# Power.net
KiCad netlist of a schematic drawn in Altium Designer
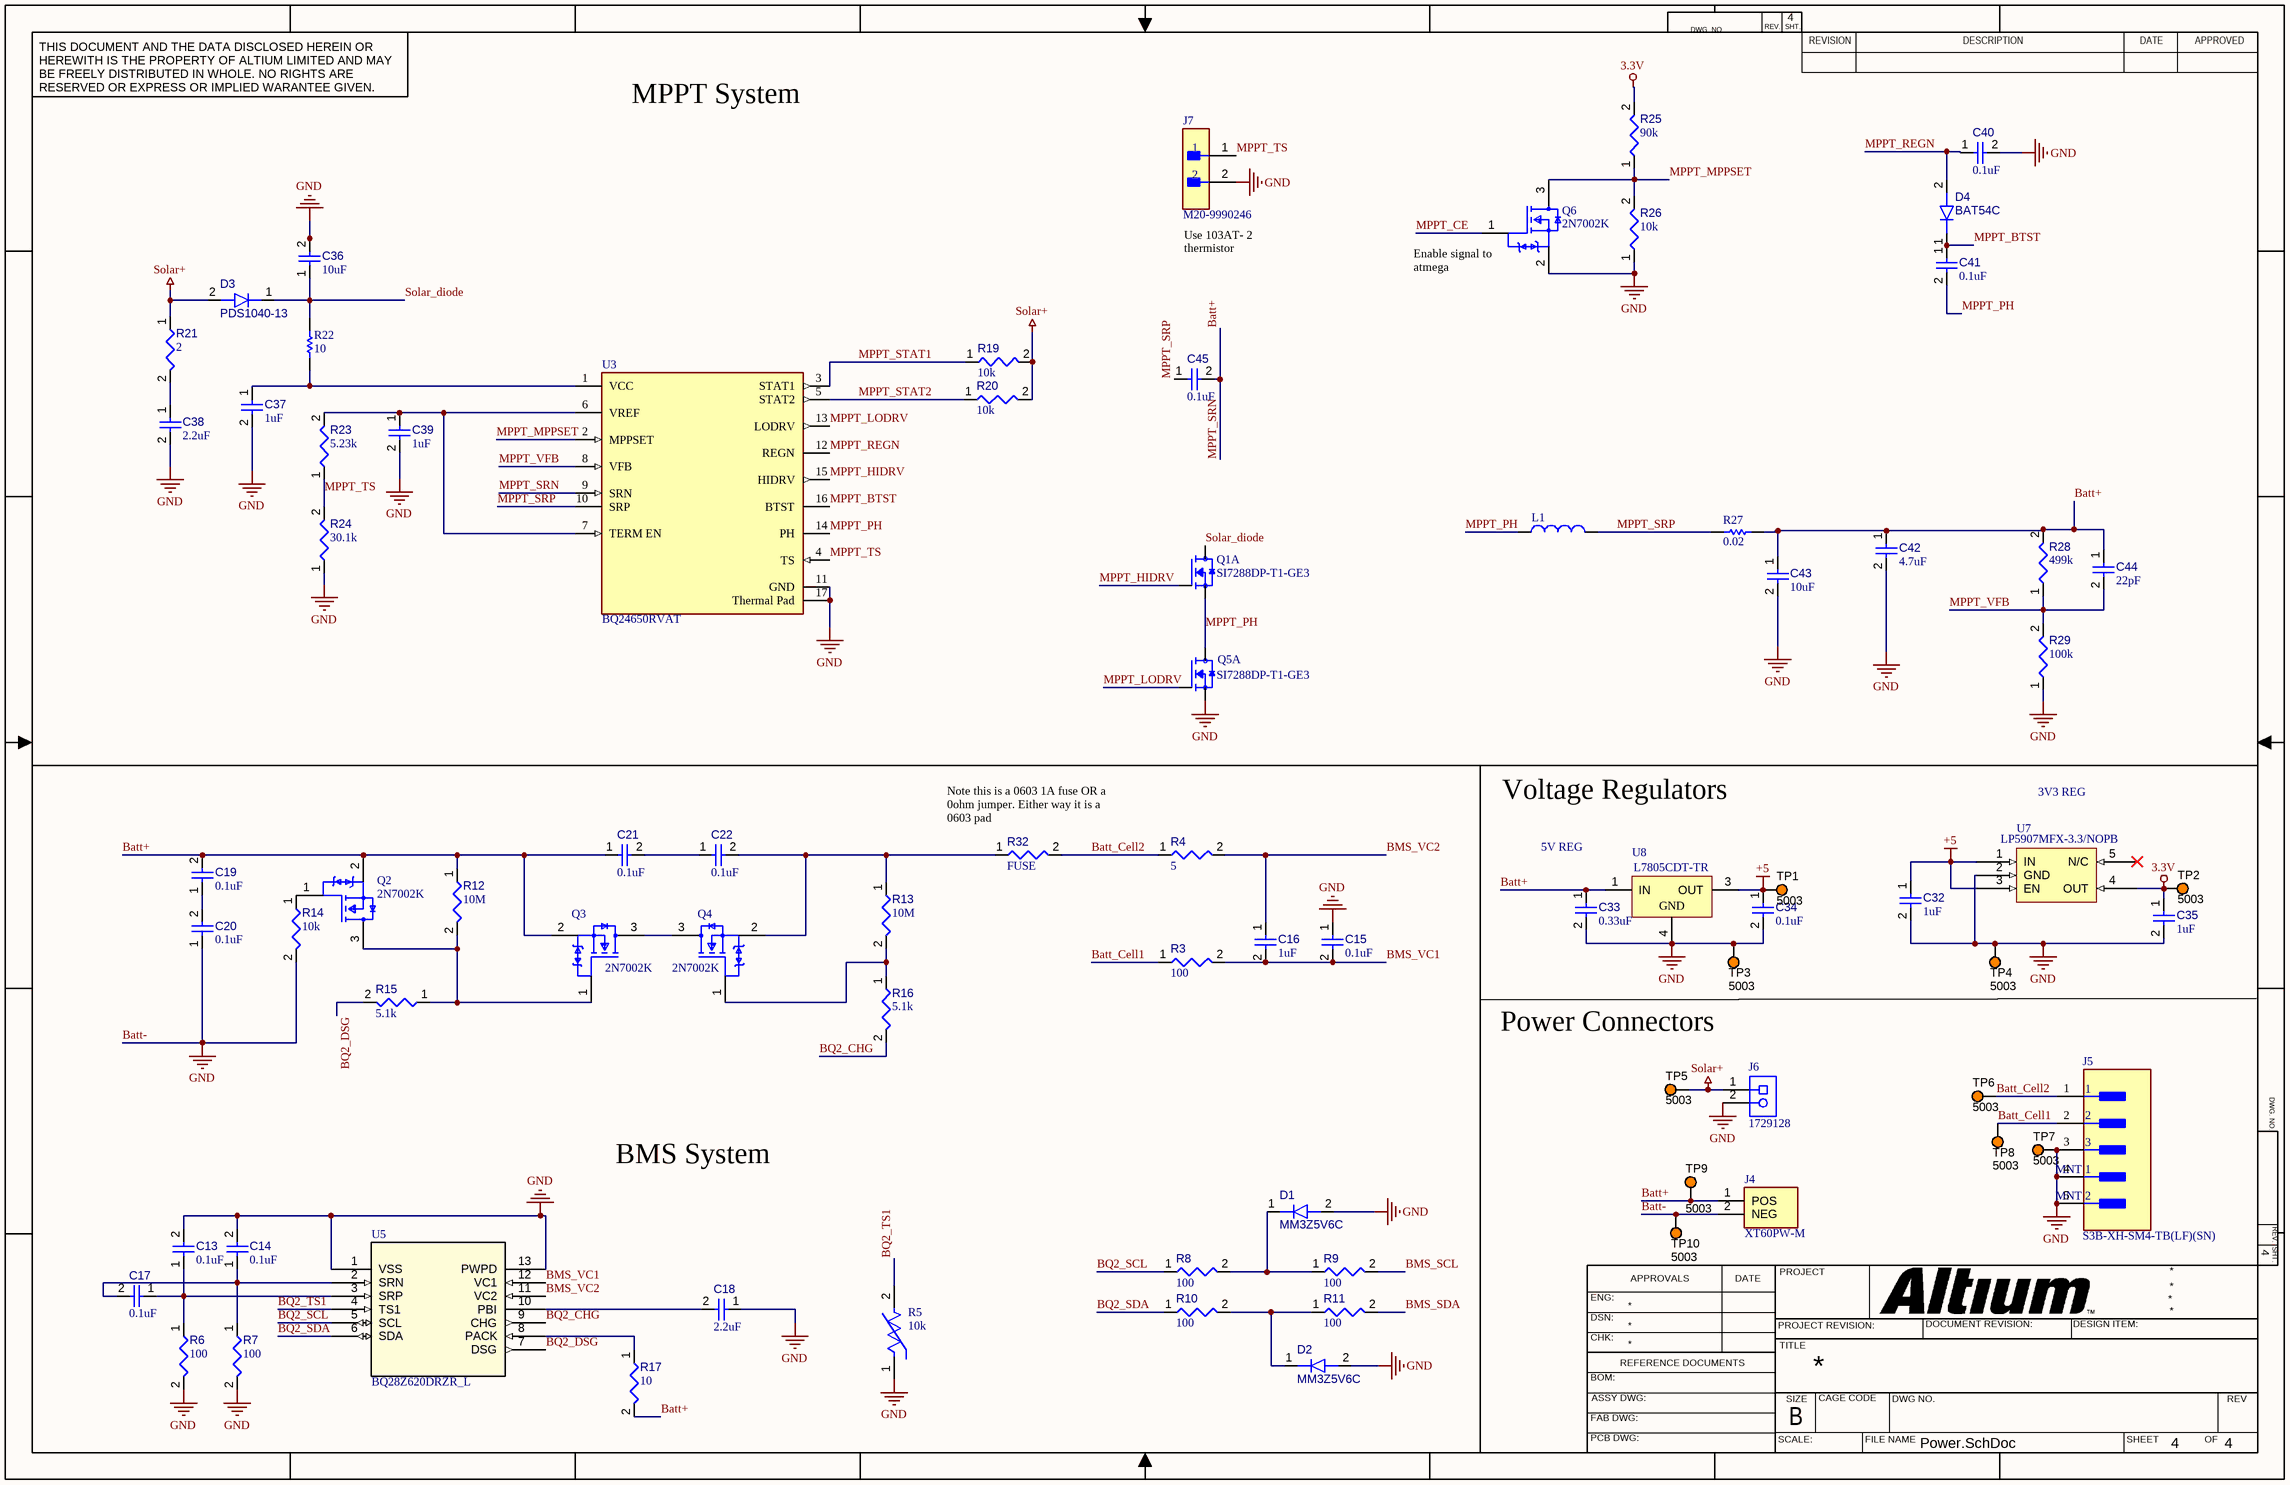
[diagram p0: Power.SchDoc]

(export (version "E")
  (design (tool "Eeschema 10.0.6"))
  (components
    (comp (ref "C13")
      (value "0.1uF")
      (footprint "CAPC1608X90X40NL10T20")
      (description "Chip Capacitor, 100 nF, +/- 10%, 50 V, 0603 (1608 Metric)")
      (fields (field (name "TOLERANCE") "10%") (field (name "Comment") "Capacitor 100 nF +/-10% 50 V 0603"))
      (libsource (lib "University of Michigan") (part "CAP-NP-2"))
    )
    (comp (ref "C14")
      (value "0.1uF")
      (footprint "CAPC1608X90X40NL10T20")
      (description "Chip Capacitor, 100 nF, +/- 10%, 50 V, 0603 (1608 Metric)")
      (fields (field (name "TOLERANCE") "10%") (field (name "Comment") "Capacitor 100 nF +/-10% 50 V 0603"))
      (libsource (lib "University of Michigan") (part "CAP-NP-2"))
    )
    (comp (ref "C15")
      (value "0.1uF")
      (footprint "CAPC1608X90X40NL10T20")
      (description "Chip Capacitor, 100 nF, +/- 10%, 50 V, 0603 (1608 Metric)")
      (fields (field (name "TOLERANCE") "10%") (field (name "Comment") "Capacitor 100 nF +/-10% 50 V 0603"))
      (libsource (lib "University of Michigan") (part "CAP-NP-2"))
    )
    (comp (ref "C16")
      (value "1uF")
      (footprint "CAPC1608X90X40NL10T20")
      (description "Chip Capacitor, 100 nF, +/- 10%, 50 V, 0603 (1608 Metric)")
      (fields (field (name "TOLERANCE") "10%") (field (name "Comment") "Capacitor 100 nF +/-10% 50 V 0603"))
      (libsource (lib "University of Michigan") (part "CAP-NP-2"))
    )
    (comp (ref "C17")
      (value "0.1uF")
      (footprint "CAPC1608X90X40NL10T20")
      (description "Chip Capacitor, 100 nF, +/- 10%, 50 V, 0603 (1608 Metric)")
      (fields (field (name "TOLERANCE") "10%") (field (name "Comment") "Capacitor 100 nF +/-10% 50 V 0603"))
      (libsource (lib "University of Michigan") (part "CAP-NP-2"))
    )
    (comp (ref "C18")
      (value "2.2uF")
      (footprint "CAPC1608X90X40NL10T20")
      (description "Chip Capacitor, 100 nF, +/- 10%, 50 V, 0603 (1608 Metric)")
      (fields (field (name "TOLERANCE") "10%") (field (name "Comment") "Capacitor 100 nF +/-10% 50 V 0603"))
      (libsource (lib "University of Michigan") (part "CAP-NP-2"))
    )
    (comp (ref "C19")
      (value "0.1uF")
      (footprint "CAPC1608X90X40NL10T20")
      (description "Chip Capacitor, 100 nF, +/- 10%, 50 V, 0603 (1608 Metric)")
      (fields (field (name "TOLERANCE") "10%") (field (name "Comment") "Capacitor 100 nF +/-10% 50 V 0603"))
      (libsource (lib "University of Michigan") (part "CAP-NP-2"))
    )
    (comp (ref "C20")
      (value "0.1uF")
      (footprint "CAPC1608X90X40NL10T20")
      (description "Chip Capacitor, 100 nF, +/- 10%, 50 V, 0603 (1608 Metric)")
      (fields (field (name "TOLERANCE") "10%") (field (name "Comment") "Capacitor 100 nF +/-10% 50 V 0603"))
      (libsource (lib "University of Michigan") (part "CAP-NP-2"))
    )
    (comp (ref "C21")
      (value "0.1uF")
      (footprint "CAPC1608X90X40NL10T20")
      (description "Chip Capacitor, 100 nF, +/- 10%, 50 V, 0603 (1608 Metric)")
      (fields (field (name "TOLERANCE") "10%") (field (name "Comment") "Capacitor 100 nF +/-10% 50 V 0603"))
      (libsource (lib "University of Michigan") (part "CAP-NP-2"))
    )
    (comp (ref "C22")
      (value "0.1uF")
      (footprint "CAPC1608X90X40NL10T20")
      (description "Chip Capacitor, 100 nF, +/- 10%, 50 V, 0603 (1608 Metric)")
      (fields (field (name "TOLERANCE") "10%") (field (name "Comment") "Capacitor 100 nF +/-10% 50 V 0603"))
      (libsource (lib "University of Michigan") (part "CAP-NP-2"))
    )
    (comp (ref "C32")
      (value "1uF")
      (footprint "CAPC1608X90X40NL10T20")
      (description "Chip Capacitor, 100 nF, +/- 10%, 50 V, 0603 (1608 Metric)")
      (fields (field (name "TOLERANCE") "10%") (field (name "Comment") "Capacitor 100 nF +/-10% 50 V 0603"))
      (libsource (lib "University of Michigan") (part "CAP-NP-2"))
    )
    (comp (ref "C33")
      (value "0.33uF")
      (footprint "CAPC1608X90X40NL10T20")
      (description "Chip Capacitor, 100 nF, +/- 10%, 50 V, 0603 (1608 Metric)")
      (fields (field (name "TOLERANCE") "10%") (field (name "Comment") "Capacitor 100 nF +/-10% 50 V 0603"))
      (libsource (lib "University of Michigan") (part "CAP-NP-2"))
    )
    (comp (ref "C34")
      (value "0.1uF")
      (footprint "CAPC1608X90X40NL10T20")
      (description "Chip Capacitor, 100 nF, +/- 10%, 50 V, 0603 (1608 Metric)")
      (fields (field (name "TOLERANCE") "10%") (field (name "Comment") "Capacitor 100 nF +/-10% 50 V 0603"))
      (libsource (lib "University of Michigan") (part "CAP-NP-2"))
    )
    (comp (ref "C35")
      (value "1uF")
      (footprint "CAPC1608X90X40NL10T20")
      (description "Chip Capacitor, 100 nF, +/- 10%, 50 V, 0603 (1608 Metric)")
      (fields (field (name "TOLERANCE") "10%") (field (name "Comment") "Capacitor 100 nF +/-10% 50 V 0603"))
      (libsource (lib "University of Michigan") (part "CAP-NP-2"))
    )
    (comp (ref "C36")
      (value "10uF")
      (footprint "FP-CGA6P-IPC_B")
      (fields (field (name "Comment") "CGA6M3X7R2E104K200AE"))
      (libsource (lib "University of Michigan") (part "CAP-NP-2"))
    )
    (comp (ref "C37")
      (value "1uF")
      (footprint "CAPC1608X90X40NL10T20")
      (description "Chip Capacitor, 100 nF, +/- 10%, 50 V, 0603 (1608 Metric)")
      (fields (field (name "TOLERANCE") "10%") (field (name "Comment") "Capacitor 100 nF +/-10% 50 V 0603"))
      (libsource (lib "University of Michigan") (part "CAP-NP-2"))
    )
    (comp (ref "C38")
      (value "2.2uF")
      (footprint "FP-CGA6P-IPC_B")
      (fields (field (name "Comment") "CGA6M3X7R2E104K200AE"))
      (libsource (lib "University of Michigan") (part "CAP-NP-2"))
    )
    (comp (ref "C39")
      (value "1uF")
      (footprint "CAPC1608X90X40NL10T20")
      (description "Chip Capacitor, 100 nF, +/- 10%, 50 V, 0603 (1608 Metric)")
      (fields (field (name "TOLERANCE") "10%") (field (name "Comment") "Capacitor 100 nF +/-10% 50 V 0603"))
      (libsource (lib "University of Michigan") (part "CAP-NP-2"))
    )
    (comp (ref "C40")
      (value "0.1uF")
      (footprint "CAPC1608X90X40NL10T20")
      (description "Chip Capacitor, 100 nF, +/- 10%, 50 V, 0603 (1608 Metric)")
      (fields (field (name "TOLERANCE") "10%") (field (name "Comment") "Capacitor 100 nF +/-10% 50 V 0603"))
      (libsource (lib "University of Michigan") (part "CAP-NP-2"))
    )
    (comp (ref "C41")
      (value "0.1uF")
      (footprint "CAPC1608X90X40NL10T20")
      (description "Chip Capacitor, 100 nF, +/- 10%, 50 V, 0603 (1608 Metric)")
      (fields (field (name "TOLERANCE") "10%") (field (name "Comment") "Capacitor 100 nF +/-10% 50 V 0603"))
      (libsource (lib "University of Michigan") (part "CAP-NP-2"))
    )
    (comp (ref "C42")
      (value "4.7uF")
      (footprint "FP-CGA6P-IPC_B")
      (fields (field (name "Comment") "CGA6M3X7R2E104K200AE"))
      (libsource (lib "University of Michigan") (part "CAP-NP-2"))
    )
    (comp (ref "C43")
      (value "10uF")
      (footprint "FP-CGA6P-IPC_B")
      (fields (field (name "Comment") "CGA6M3X7R2E104K200AE"))
      (libsource (lib "University of Michigan") (part "CAP-NP-2"))
    )
    (comp (ref "C44")
      (value "22pF")
      (footprint "CAPC1608X90X40NL10T20")
      (description "Chip Capacitor, 100 nF, +/- 10%, 50 V, 0603 (1608 Metric)")
      (fields (field (name "TOLERANCE") "10%") (field (name "Comment") "Capacitor 100 nF +/-10% 50 V 0603"))
      (libsource (lib "University of Michigan") (part "CAP-NP-2"))
    )
    (comp (ref "C45")
      (value "0.1uF")
      (footprint "CAPC1608X90X40NL10T20")
      (description "Chip Capacitor, 100 nF, +/- 10%, 50 V, 0603 (1608 Metric)")
      (fields (field (name "TOLERANCE") "10%") (field (name "Comment") "Capacitor 100 nF +/-10% 50 V 0603"))
      (libsource (lib "University of Michigan") (part "CAP-NP-2"))
    )
    (comp (ref "D1")
      (value "MM3Z5V6C")
      (footprint "FP-SOD-323F-MFG")
      (description "Zener Diode, 5.6V V(Z), 5%, 0.2W, Silicon, Unidirectional")
      (libsource (lib "University of Michigan") (part "DIODE-2"))
    )
    (comp (ref "D2")
      (value "MM3Z5V6C")
      (footprint "FP-SOD-323F-MFG")
      (description "Zener Diode, 5.6V V(Z), 5%, 0.2W, Silicon, Unidirectional")
      (libsource (lib "University of Michigan") (part "DIODE-2"))
    )
    (comp (ref "D3")
      (value "PDS1040-13")
      (footprint "FP-PowerDI5-MFG")
      (description "Rectifier Diode, Schottky, 1 Phase, 1 Element, 10A, 40V V(RRM), Silicon")
      (libsource (lib "University of Michigan") (part "DIODE-2"))
    )
    (comp (ref "D4")
      (value "BAT54C")
      (footprint "NXP-SOT23-3_V")
      (description "Rectifier Diode, Schottky, 2 Element, 0.2A, 30V V(RRM), Silicon, TO-236AB")
      (libsource (lib "University of Michigan") (part "DIODE-2"))
    )
    (comp (ref "J4")
      (value "XT60PW-M")
      (footprint "AMASS_XT60PW-M")
      (description "Socket, DC supply, male, PIN: 2")
      (fields (field (name "MF") "AMASS"))
      (libsource (lib "University of Michigan") (part "XT60PW-M"))
    )
    (comp (ref "J5")
      (value "S3B-XH-SM4-TB(LF)(SN)")
      (footprint "FP-S3B-XH-SM4-TB_LF_SN-MFG")
      (description "Conn Shrouded Header HDR 3 POS 2.5mm Solder RA Side Entry SMD T/R")
      (libsource (lib "University of Michigan") (part "49575d61908034f7a5505a4f8bf3aa4"))
    )
    (comp (ref "J6")
      (value "1729128")
      (footprint "PHOE-1729128-2_V")
      (description "Barrier Strip Terminal Block, 13.5A, 1.5mm2, 1 Row(s), 1 Deck(s)")
      (libsource (lib "University of Michigan") (part "CN-2P-F-R2"))
    )
    (comp (ref "J7")
      (value "M20-9990246")
      (footprint "FP-M20-9990246-MFG")
      (libsource (lib "University of Michigan") (part "3bc925449376181038e59eaffc5286c"))
    )
    (comp (ref "L1")
      (value "IHLP2525CZER100M01")
      (footprint "VISH-IHLP2525C-01_V")
      (description "General Purpose Inductor, 10uH, 20%, 1 Element, Composite-Core, SMD, 2525")
      (fields (field (name "TOLERANCE") "20%"))
      (libsource (lib "University of Michigan") (part "IND-2"))
    )
    (comp (ref "Q1")
      (value "SI7288DP-T1-GE3")
      (footprint "TRANS_SI7288DP-T1-GE3")
      (description "Mosfet Array 2 N-Channel (Dual) 40V 20A 15.6W Surface Mount PowerPAKÂ® SO-8 Dual")
      (fields (field (name "MF") "Vishay") (field (name "DIGI-KEY_PART_NUMBER") "SI7288DP-T1-GE3TR-ND"))
      (libsource (lib "University of Michigan") (part "SI7288DP-T1-GE3"))
    )
    (comp (ref "Q2")
      (value "2N7002K")
      (footprint "FP-318-08-IPC_C")
      (libsource (lib "University of Michigan") (part "40bafa8609a25cdbb0dab398ef4a0d9"))
    )
    (comp (ref "Q3")
      (value "2N7002K")
      (footprint "FP-318-08-IPC_C")
      (libsource (lib "University of Michigan") (part "40bafa8609a25cdbb0dab398ef4a0d9"))
    )
    (comp (ref "Q4")
      (value "2N7002K")
      (footprint "FP-318-08-IPC_C")
      (libsource (lib "University of Michigan") (part "40bafa8609a25cdbb0dab398ef4a0d9"))
    )
    (comp (ref "Q5")
      (value "SI7288DP-T1-GE3")
      (footprint "TRANS_SI7288DP-T1-GE3")
      (description "Mosfet Array 2 N-Channel (Dual) 40V 20A 15.6W Surface Mount PowerPAKÂ® SO-8 Dual")
      (fields (field (name "MF") "Vishay") (field (name "DIGI-KEY_PART_NUMBER") "SI7288DP-T1-GE3TR-ND"))
      (libsource (lib "University of Michigan") (part "SI7288DP-T1-GE3"))
    )
    (comp (ref "Q6")
      (value "2N7002K")
      (footprint "FP-318-08-IPC_C")
      (libsource (lib "University of Michigan") (part "40bafa8609a25cdbb0dab398ef4a0d9"))
    )
    (comp (ref "R3")
      (value "100")
      (footprint "RESC0603(1608)_L")
      (description "Chip Resistor, 120 Ohms, +/-5 %, 0.1 W, -55 to 155 degC, 0603")
      (fields (field (name "POWER") "100mW") (field (name "TOLERANCE") "5%"))
      (libsource (lib "University of Michigan") (part "RES-2"))
    )
    (comp (ref "R4")
      (value "5")
      (footprint "RESC0603(1608)_L")
      (description "Chip Resistor, 120 Ohms, +/-5 %, 0.1 W, -55 to 155 degC, 0603")
      (fields (field (name "POWER") "100mW") (field (name "TOLERANCE") "5%"))
      (libsource (lib "University of Michigan") (part "RES-2"))
    )
    (comp (ref "R5")
      (value "10k")
      (footprint "FP-103AT-2-MFG")
      (description "NTC Thermistor, 10000ohm, Through Hole Mount")
      (fields (field (name "POWER") "10mW") (field (name "TOLERANCE") "1%"))
      (libsource (lib "University of Michigan") (part "3b148a6ebabc5fb4d708a66c052d352"))
    )
    (comp (ref "R6")
      (value "100")
      (footprint "RESC0603(1608)_L")
      (description "Chip Resistor, 120 Ohms, +/-5 %, 0.1 W, -55 to 155 degC, 0603")
      (fields (field (name "POWER") "100mW") (field (name "TOLERANCE") "5%"))
      (libsource (lib "University of Michigan") (part "RES-2"))
    )
    (comp (ref "R7")
      (value "100")
      (footprint "RESC0603(1608)_L")
      (description "Chip Resistor, 120 Ohms, +/-5 %, 0.1 W, -55 to 155 degC, 0603")
      (fields (field (name "POWER") "100mW") (field (name "TOLERANCE") "5%"))
      (libsource (lib "University of Michigan") (part "RES-2"))
    )
    (comp (ref "R8")
      (value "100")
      (footprint "RESC0603(1608)_L")
      (description "Chip Resistor, 120 Ohms, +/-5 %, 0.1 W, -55 to 155 degC, 0603")
      (fields (field (name "POWER") "100mW") (field (name "TOLERANCE") "5%"))
      (libsource (lib "University of Michigan") (part "RES-2"))
    )
    (comp (ref "R9")
      (value "100")
      (footprint "RESC0603(1608)_L")
      (description "Chip Resistor, 120 Ohms, +/-5 %, 0.1 W, -55 to 155 degC, 0603")
      (fields (field (name "POWER") "100mW") (field (name "TOLERANCE") "5%"))
      (libsource (lib "University of Michigan") (part "RES-2"))
    )
    (comp (ref "R10")
      (value "100")
      (footprint "RESC0603(1608)_L")
      (description "Chip Resistor, 120 Ohms, +/-5 %, 0.1 W, -55 to 155 degC, 0603")
      (fields (field (name "POWER") "100mW") (field (name "TOLERANCE") "5%"))
      (libsource (lib "University of Michigan") (part "RES-2"))
    )
    (comp (ref "R11")
      (value "100")
      (footprint "RESC0603(1608)_L")
      (description "Chip Resistor, 120 Ohms, +/-5 %, 0.1 W, -55 to 155 degC, 0603")
      (fields (field (name "POWER") "100mW") (field (name "TOLERANCE") "5%"))
      (libsource (lib "University of Michigan") (part "RES-2"))
    )
    (comp (ref "R12")
      (value "10M")
      (footprint "RESC0603(1608)_L")
      (description "Chip Resistor, 120 Ohms, +/-5 %, 0.1 W, -55 to 155 degC, 0603")
      (fields (field (name "POWER") "100mW") (field (name "TOLERANCE") "5%"))
      (libsource (lib "University of Michigan") (part "RES-2"))
    )
    (comp (ref "R13")
      (value "10M")
      (footprint "RESC0603(1608)_L")
      (description "Chip Resistor, 120 Ohms, +/-5 %, 0.1 W, -55 to 155 degC, 0603")
      (fields (field (name "POWER") "100mW") (field (name "TOLERANCE") "5%"))
      (libsource (lib "University of Michigan") (part "RES-2"))
    )
    (comp (ref "R14")
      (value "10k")
      (footprint "RESC0603(1608)_L")
      (description "Chip Resistor, 120 Ohms, +/-5 %, 0.1 W, -55 to 155 degC, 0603")
      (fields (field (name "POWER") "100mW") (field (name "TOLERANCE") "5%"))
      (libsource (lib "University of Michigan") (part "RES-2"))
    )
    (comp (ref "R15")
      (value "5.1k")
      (footprint "RESC0603(1608)_L")
      (description "Chip Resistor, 120 Ohms, +/-5 %, 0.1 W, -55 to 155 degC, 0603")
      (fields (field (name "POWER") "100mW") (field (name "TOLERANCE") "5%"))
      (libsource (lib "University of Michigan") (part "RES-2"))
    )
    (comp (ref "R16")
      (value "5.1k")
      (footprint "RESC0603(1608)_L")
      (description "Chip Resistor, 120 Ohms, +/-5 %, 0.1 W, -55 to 155 degC, 0603")
      (fields (field (name "POWER") "100mW") (field (name "TOLERANCE") "5%"))
      (libsource (lib "University of Michigan") (part "RES-2"))
    )
    (comp (ref "R17")
      (value "10")
      (footprint "RESC0603(1608)_L")
      (description "Chip Resistor, 120 Ohms, +/-5 %, 0.1 W, -55 to 155 degC, 0603")
      (fields (field (name "POWER") "100mW") (field (name "TOLERANCE") "5%"))
      (libsource (lib "University of Michigan") (part "RES-2"))
    )
    (comp (ref "R19")
      (value "10k")
      (footprint "RESC0603(1608)_L")
      (description "Chip Resistor, 120 Ohms, +/-5 %, 0.1 W, -55 to 155 degC, 0603")
      (fields (field (name "POWER") "100mW") (field (name "TOLERANCE") "5%"))
      (libsource (lib "University of Michigan") (part "RES-2"))
    )
    (comp (ref "R20")
      (value "10k")
      (footprint "RESC0603(1608)_L")
      (description "Chip Resistor, 120 Ohms, +/-5 %, 0.1 W, -55 to 155 degC, 0603")
      (fields (field (name "POWER") "100mW") (field (name "TOLERANCE") "5%"))
      (libsource (lib "University of Michigan") (part "RES-2"))
    )
    (comp (ref "R21")
      (value "2")
      (footprint "FP-CRCW2512-e3-MFG")
      (fields
        (field (name "TOLERANCE") "5%")
        (field (name "POWER") "1W")
        (field (name "Comment") "CRCW251291R0JNEG")
      )
      (libsource (lib "University of Michigan") (part "RES-2"))
    )
    (comp (ref "R22")
      (value "10")
      (footprint "RESC3116X70X50ML13T20")
      (description "Chip Resistor, 0 Ohm, 0.25 W, -55 to 155 degC, 1206 (3216 Metric)")
      (fields (field (name "TOLERANCE") "0.05%") (field (name "POWER") "250mW"))
      (libsource (lib "") (part "RES-2_1"))
    )
    (comp (ref "R23")
      (value "5.23k")
      (footprint "RESC0603(1608)_L")
      (description "Chip Resistor, 120 Ohms, +/-5 %, 0.1 W, -55 to 155 degC, 0603")
      (fields (field (name "POWER") "100mW") (field (name "TOLERANCE") "5%"))
      (libsource (lib "University of Michigan") (part "RES-2"))
    )
    (comp (ref "R24")
      (value "30.1k")
      (footprint "RESC0603(1608)_L")
      (description "Chip Resistor, 120 Ohms, +/-5 %, 0.1 W, -55 to 155 degC, 0603")
      (fields (field (name "POWER") "100mW") (field (name "TOLERANCE") "5%"))
      (libsource (lib "University of Michigan") (part "RES-2"))
    )
    (comp (ref "R25")
      (value "90k")
      (footprint "RESC0603(1608)_L")
      (description "Chip Resistor, 120 Ohms, +/-5 %, 0.1 W, -55 to 155 degC, 0603")
      (fields (field (name "POWER") "100mW") (field (name "TOLERANCE") "5%"))
      (libsource (lib "University of Michigan") (part "RES-2"))
    )
    (comp (ref "R26")
      (value "10k")
      (footprint "RESC0603(1608)_L")
      (description "Chip Resistor, 120 Ohms, +/-5 %, 0.1 W, -55 to 155 degC, 0603")
      (fields (field (name "POWER") "100mW") (field (name "TOLERANCE") "5%"))
      (libsource (lib "University of Michigan") (part "RES-2"))
    )
    (comp (ref "R27")
      (value "0.02")
      (footprint "RESC3116X70X50ML13T20")
      (description "Chip Resistor, 1 KOhm, +/- 1%, 0.25 W, -55 to 155 degC, 1206 (3216 Metric)")
      (fields (field (name "TOLERANCE") "1%") (field (name "POWER") "250mW"))
      (libsource (lib "") (part "RES-2_1"))
    )
    (comp (ref "R28")
      (value "499k")
      (footprint "RESC0603(1608)_L")
      (description "Chip Resistor, 120 Ohms, +/-5 %, 0.1 W, -55 to 155 degC, 0603")
      (fields (field (name "POWER") "100mW") (field (name "TOLERANCE") "5%"))
      (libsource (lib "University of Michigan") (part "RES-2"))
    )
    (comp (ref "R29")
      (value "100k")
      (footprint "RESC0603(1608)_L")
      (description "Chip Resistor, 120 Ohms, +/-5 %, 0.1 W, -55 to 155 degC, 0603")
      (fields (field (name "POWER") "100mW") (field (name "TOLERANCE") "5%"))
      (libsource (lib "University of Michigan") (part "RES-2"))
    )
    (comp (ref "R32")
      (value "FUSE")
      (footprint "RESC0603(1608)_L")
      (description "Chip Resistor, 120 Ohms, +/-5 %, 0.1 W, -55 to 155 degC, 0603")
      (fields (field (name "POWER") "100mW") (field (name "TOLERANCE") "5%"))
      (libsource (lib "University of Michigan") (part "RES-2"))
    )
    (comp (ref "TP1")
      (value "5003")
      (footprint "KSTN-5003")
      (description "Test Point, Orange, Height 4.6 mm, Tail Length 3 mm, 1-Pin THD, RoHS")
      (fields (field (name "MANUFACTURER") "Keystone"))
      (libsource (lib "University of Michigan") (part "TESTPOINT_ORANGE"))
    )
    (comp (ref "TP2")
      (value "5003")
      (footprint "KSTN-5003")
      (description "Test Point, Orange, Height 4.6 mm, Tail Length 3 mm, 1-Pin THD, RoHS")
      (fields (field (name "MANUFACTURER") "Keystone"))
      (libsource (lib "University of Michigan") (part "TESTPOINT_ORANGE"))
    )
    (comp (ref "TP3")
      (value "5003")
      (footprint "KSTN-5003")
      (description "Test Point, Orange, Height 4.6 mm, Tail Length 3 mm, 1-Pin THD, RoHS")
      (fields (field (name "MANUFACTURER") "Keystone"))
      (libsource (lib "University of Michigan") (part "TESTPOINT_ORANGE"))
    )
    (comp (ref "TP4")
      (value "5003")
      (footprint "KSTN-5003")
      (description "Test Point, Orange, Height 4.6 mm, Tail Length 3 mm, 1-Pin THD, RoHS")
      (fields (field (name "MANUFACTURER") "Keystone"))
      (libsource (lib "University of Michigan") (part "TESTPOINT_ORANGE"))
    )
    (comp (ref "TP5")
      (value "5003")
      (footprint "KSTN-5003")
      (description "Test Point, Orange, Height 4.6 mm, Tail Length 3 mm, 1-Pin THD, RoHS")
      (fields (field (name "MANUFACTURER") "Keystone"))
      (libsource (lib "University of Michigan") (part "TESTPOINT_ORANGE"))
    )
    (comp (ref "TP6")
      (value "5003")
      (footprint "KSTN-5003")
      (description "Test Point, Orange, Height 4.6 mm, Tail Length 3 mm, 1-Pin THD, RoHS")
      (fields (field (name "MANUFACTURER") "Keystone"))
      (libsource (lib "University of Michigan") (part "TESTPOINT_ORANGE"))
    )
    (comp (ref "TP7")
      (value "5003")
      (footprint "KSTN-5003")
      (description "Test Point, Orange, Height 4.6 mm, Tail Length 3 mm, 1-Pin THD, RoHS")
      (fields (field (name "MANUFACTURER") "Keystone"))
      (libsource (lib "University of Michigan") (part "TESTPOINT_ORANGE"))
    )
    (comp (ref "TP8")
      (value "5003")
      (footprint "KSTN-5003")
      (description "Test Point, Orange, Height 4.6 mm, Tail Length 3 mm, 1-Pin THD, RoHS")
      (fields (field (name "MANUFACTURER") "Keystone"))
      (libsource (lib "University of Michigan") (part "TESTPOINT_ORANGE"))
    )
    (comp (ref "TP9")
      (value "5003")
      (footprint "KSTN-5003")
      (description "Test Point, Orange, Height 4.6 mm, Tail Length 3 mm, 1-Pin THD, RoHS")
      (fields (field (name "MANUFACTURER") "Keystone"))
      (libsource (lib "University of Michigan") (part "TESTPOINT_ORANGE"))
    )
    (comp (ref "TP10")
      (value "5003")
      (footprint "KSTN-5003")
      (description "Test Point, Orange, Height 4.6 mm, Tail Length 3 mm, 1-Pin THD, RoHS")
      (fields (field (name "MANUFACTURER") "Keystone"))
      (libsource (lib "University of Michigan") (part "TESTPOINT_ORANGE"))
    )
    (comp (ref "U3")
      (value "BQ24650RVAT")
      (footprint "FP-RVA0016A-IPC_B")
      (description "Power Supply Support Circuit, Adjustable, 1 Channel, +3.85V, PQCC16")
      (libsource (lib "University of Michigan") (part "cf19bb46e92d87c2bf2948a47118a18"))
    )
    (comp (ref "U5")
      (value "BQ28Z620DRZR_L")
      (footprint "VSON12_DRZ_TEX_L")
      (description "No Description Available")
      (fields
        (field (name "MANUFACTURER_PART_NUMBER") "BQ28Z620DRZR")
        (field (name "COPYRIGHT") "Copyright (C) 2023 Ultra Librarian. All rights reserved.")
      )
      (libsource (lib "University of Michigan") (part "BQ28Z620DRZR_L"))
    )
    (comp (ref "U7")
      (value "LP5907MFX-3.3/NOPB")
      (footprint "FP-DBV0005A-IPC_B")
      (description "Fixed Positive LDO Regulator, 3.3V, 0.25V Dropout, PDSO5")
      (libsource (lib "University of Michigan") (part "LP5907MFX-3.3_NOPB-Symbol-1"))
    )
    (comp (ref "U8")
      (value "L7805CDT-TR")
      (footprint "TO-252_L")
      (description "Fixed Positive Standard Regulator, 5VBIPolar, PSSO2")
      (libsource (lib "University of Michigan") (part "PM-REG-L4940-SOT3"))
    )
  )
  (nets
    (net (code "1") (name "+5") (class "Default")
      (node (ref "C32") (pin "1") (pinfunction "1_1") (pintype "passive"))
      (node (ref "C34") (pin "1") (pinfunction "1_1") (pintype "passive"))
      (node (ref "TP1") (pin "1") (pinfunction "1_1") (pintype "passive"))
      (node (ref "U7") (pin "1") (pinfunction "IN_1") (pintype "input"))
      (node (ref "U7") (pin "3") (pinfunction "EN_3") (pintype "input"))
      (node (ref "U8") (pin "3") (pinfunction "OUT_3") (pintype "power_in"))
    )
    (net (code "2") (name "/BMS_SCL") (class "Default")
      (node (ref "R9") (pin "2") (pinfunction "2_2") (pintype "passive"))
    )
    (net (code "3") (name "/BMS_SDA") (class "Default")
      (node (ref "R11") (pin "2") (pinfunction "2_2") (pintype "passive"))
    )
    (net (code "4") (name "/BMS_VC1") (class "Default")
      (node (ref "C15") (pin "2") (pinfunction "2_2") (pintype "passive"))
      (node (ref "C16") (pin "2") (pinfunction "2_2") (pintype "passive"))
      (node (ref "R3") (pin "2") (pinfunction "2_2") (pintype "passive"))
      (node (ref "U5") (pin "12") (pinfunction "VC1_12") (pintype "input"))
    )
    (net (code "5") (name "/BMS_VC2") (class "Default")
      (node (ref "C16") (pin "1") (pinfunction "1_1") (pintype "passive"))
      (node (ref "R4") (pin "2") (pinfunction "2_2") (pintype "passive"))
      (node (ref "U5") (pin "11") (pinfunction "VC2_11") (pintype "input"))
    )
    (net (code "6") (name "/BQ2_CHG") (class "Default")
      (node (ref "R16") (pin "2") (pinfunction "2_2") (pintype "passive"))
      (node (ref "U5") (pin "9") (pinfunction "CHG_9") (pintype "output"))
    )
    (net (code "7") (name "/BQ2_DSG") (class "Default")
      (node (ref "R15") (pin "2") (pinfunction "2_2") (pintype "passive"))
      (node (ref "U5") (pin "7") (pinfunction "DSG_7") (pintype "output"))
    )
    (net (code "8") (name "/BQ2_SCL") (class "Default")
      (node (ref "R8") (pin "1") (pinfunction "1_1") (pintype "passive"))
      (node (ref "U5") (pin "5") (pinfunction "SCL_5") (pintype "bidirectional"))
    )
    (net (code "9") (name "/BQ2_SDA") (class "Default")
      (node (ref "R10") (pin "1") (pinfunction "1_1") (pintype "passive"))
      (node (ref "U5") (pin "6") (pinfunction "SDA_6") (pintype "bidirectional"))
    )
    (net (code "10") (name "/BQ2_TS1") (class "Default")
      (node (ref "R5") (pin "2") (pinfunction "2_2") (pintype "passive"))
      (node (ref "U5") (pin "4") (pinfunction "TS1_4") (pintype "input"))
    )
    (net (code "11") (name "/Batt+") (class "Default")
      (node (ref "C19") (pin "2") (pinfunction "2_2") (pintype "passive"))
      (node (ref "C21") (pin "1") (pinfunction "1_1") (pintype "passive"))
      (node (ref "C33") (pin "1") (pinfunction "1_1") (pintype "passive"))
      (node (ref "C42") (pin "1") (pinfunction "1_1") (pintype "passive"))
      (node (ref "C43") (pin "1") (pinfunction "1_1") (pintype "passive"))
      (node (ref "C44") (pin "1") (pinfunction "1_1") (pintype "passive"))
      (node (ref "C45") (pin "2") (pinfunction "2_2") (pintype "passive"))
      (node (ref "J4") (pin "1") (pinfunction "POS_1") (pintype "passive"))
      (node (ref "Q2") (pin "2") (pinfunction "Source_2") (pintype "passive"))
      (node (ref "Q3") (pin "2") (pinfunction "Source_2") (pintype "passive"))
      (node (ref "R12") (pin "1") (pinfunction "1_1") (pintype "passive"))
      (node (ref "R17") (pin "2") (pinfunction "2_2") (pintype "passive"))
      (node (ref "R27") (pin "2") (pinfunction "2_2") (pintype "passive"))
      (node (ref "R28") (pin "2") (pinfunction "2_2") (pintype "passive"))
      (node (ref "TP9") (pin "1") (pinfunction "1_1") (pintype "passive"))
      (node (ref "U3") (pin "9") (pinfunction "SRN_9") (pintype "input"))
      (node (ref "U8") (pin "1") (pinfunction "IN_1") (pintype "power_in"))
    )
    (net (code "12") (name "/Batt_Cell1") (class "Default")
      (node (ref "J5") (pin "2") (pinfunction "2_2") (pintype "passive"))
      (node (ref "R3") (pin "1") (pinfunction "1_1") (pintype "passive"))
      (node (ref "TP8") (pin "1") (pinfunction "1_1") (pintype "passive"))
    )
    (net (code "13") (name "/Batt_Cell2") (class "Default")
      (node (ref "J5") (pin "1") (pinfunction "1_1") (pintype "passive"))
      (node (ref "R32") (pin "2") (pinfunction "2_2") (pintype "passive"))
      (node (ref "R4") (pin "1") (pinfunction "1_1") (pintype "passive"))
      (node (ref "TP6") (pin "1") (pinfunction "1_1") (pintype "passive"))
    )
    (net (code "14") (name "/MPPT_BTST") (class "Default")
      (node (ref "C41") (pin "1") (pinfunction "1_1") (pintype "passive"))
      (node (ref "D4") (pin "1") (pinfunction "K_1") (pintype "passive"))
      (node (ref "U3") (pin "16") (pinfunction "BTST_16") (pintype "power_in"))
    )
    (net (code "15") (name "/MPPT_CE") (class "Default")
      (node (ref "Q6") (pin "1") (pinfunction "Gate_1") (pintype "passive"))
    )
    (net (code "16") (name "/MPPT_HIDRV") (class "Default")
      (node (ref "Q1") (pin "2") (pinfunction "G1_2") (pintype "passive"))
      (node (ref "U3") (pin "15") (pinfunction "HIDRV_15") (pintype "output"))
    )
    (net (code "17") (name "/MPPT_LODRV") (class "Default")
      (node (ref "Q5") (pin "2") (pinfunction "G1_2") (pintype "passive"))
      (node (ref "U3") (pin "13") (pinfunction "LODRV_13") (pintype "output"))
    )
    (net (code "18") (name "/MPPT_MPPSET") (class "Default")
      (node (ref "Q6") (pin "3") (pinfunction "Drain_3") (pintype "passive"))
      (node (ref "R25") (pin "1") (pinfunction "1_1") (pintype "passive"))
      (node (ref "R26") (pin "2") (pinfunction "2_2") (pintype "passive"))
      (node (ref "U3") (pin "2") (pinfunction "MPPSET_2") (pintype "input"))
    )
    (net (code "19") (name "/MPPT_PH") (class "Default")
      (node (ref "C41") (pin "2") (pinfunction "2_2") (pintype "passive"))
      (node (ref "L1") (pin "1") (pinfunction "1_1") (pintype "passive"))
      (node (ref "Q1") (pin "1") (pinfunction "S1_1") (pintype "passive"))
      (node (ref "Q5") (pin "7_8_9") (pinfunction "D1_7_8_9") (pintype "passive"))
      (node (ref "U3") (pin "14") (pinfunction "PH_14") (pintype "power_in"))
    )
    (net (code "20") (name "/MPPT_REGN") (class "Default")
      (node (ref "C40") (pin "1") (pinfunction "1_1") (pintype "passive"))
      (node (ref "D4") (pin "2") (pinfunction "A_2") (pintype "passive"))
      (node (ref "U3") (pin "12") (pinfunction "REGN_12") (pintype "power_in"))
    )
    (net (code "21") (name "/MPPT_SRP") (class "Default")
      (node (ref "C45") (pin "1") (pinfunction "1_1") (pintype "passive"))
      (node (ref "L1") (pin "2") (pinfunction "2_2") (pintype "passive"))
      (node (ref "R27") (pin "1") (pinfunction "1_1") (pintype "passive"))
      (node (ref "U3") (pin "10") (pinfunction "SRP_10") (pintype "passive"))
    )
    (net (code "22") (name "/MPPT_STAT1") (class "Default")
      (node (ref "R19") (pin "1") (pinfunction "1_1") (pintype "passive"))
      (node (ref "U3") (pin "3") (pinfunction "STAT1_3") (pintype "output"))
    )
    (net (code "23") (name "/MPPT_STAT2") (class "Default")
      (node (ref "R20") (pin "1") (pinfunction "1_1") (pintype "passive"))
      (node (ref "U3") (pin "5") (pinfunction "STAT2_5") (pintype "output"))
    )
    (net (code "24") (name "/MPPT_TS") (class "Default")
      (node (ref "J7") (pin "1") (pinfunction "1_1") (pintype "passive"))
      (node (ref "R23") (pin "1") (pinfunction "1_1") (pintype "passive"))
      (node (ref "R24") (pin "2") (pinfunction "2_2") (pintype "passive"))
      (node (ref "U3") (pin "4") (pinfunction "TS_4") (pintype "input"))
    )
    (net (code "25") (name "/MPPT_VFB") (class "Default")
      (node (ref "C44") (pin "2") (pinfunction "2_2") (pintype "passive"))
      (node (ref "R28") (pin "1") (pinfunction "1_1") (pintype "passive"))
      (node (ref "R29") (pin "2") (pinfunction "2_2") (pintype "passive"))
      (node (ref "U3") (pin "8") (pinfunction "VFB_8") (pintype "input"))
    )
    (net (code "26") (name "/Solar_diode") (class "Default")
      (node (ref "C36") (pin "1") (pinfunction "1_1") (pintype "passive"))
      (node (ref "D3") (pin "1") (pinfunction "K_1") (pintype "passive"))
      (node (ref "Q1") (pin "7_8_9") (pinfunction "D1_7_8_9") (pintype "passive"))
      (node (ref "R22") (pin "1") (pinfunction "1_1") (pintype "passive"))
    )
    (net (code "27") (name "3.3V") (class "Default")
      (node (ref "C35") (pin "1") (pinfunction "1_1") (pintype "passive"))
      (node (ref "R25") (pin "2") (pinfunction "2_2") (pintype "passive"))
      (node (ref "TP2") (pin "1") (pinfunction "1_1") (pintype "passive"))
      (node (ref "U7") (pin "4") (pinfunction "OUT_4") (pintype "input"))
    )
    (net (code "28") (name "GND") (class "Default")
      (node (ref "C13") (pin "2") (pinfunction "2_2") (pintype "passive"))
      (node (ref "C14") (pin "2") (pinfunction "2_2") (pintype "passive"))
      (node (ref "C15") (pin "1") (pinfunction "1_1") (pintype "passive"))
      (node (ref "C18") (pin "1") (pinfunction "1_1") (pintype "passive"))
      (node (ref "C20") (pin "1") (pinfunction "1_1") (pintype "passive"))
      (node (ref "C32") (pin "2") (pinfunction "2_2") (pintype "passive"))
      (node (ref "C33") (pin "2") (pinfunction "2_2") (pintype "passive"))
      (node (ref "C34") (pin "2") (pinfunction "2_2") (pintype "passive"))
      (node (ref "C35") (pin "2") (pinfunction "2_2") (pintype "passive"))
      (node (ref "C36") (pin "2") (pinfunction "2_2") (pintype "passive"))
      (node (ref "C37") (pin "2") (pinfunction "2_2") (pintype "passive"))
      (node (ref "C38") (pin "2") (pinfunction "2_2") (pintype "passive"))
      (node (ref "C39") (pin "2") (pinfunction "2_2") (pintype "passive"))
      (node (ref "C40") (pin "2") (pinfunction "2_2") (pintype "passive"))
      (node (ref "C42") (pin "2") (pinfunction "2_2") (pintype "passive"))
      (node (ref "C43") (pin "2") (pinfunction "2_2") (pintype "passive"))
      (node (ref "D1") (pin "2") (pinfunction "A_2") (pintype "passive"))
      (node (ref "D2") (pin "2") (pinfunction "A_2") (pintype "passive"))
      (node (ref "J4") (pin "2") (pinfunction "NEG_2") (pintype "passive"))
      (node (ref "J5") (pin "3") (pinfunction "3_3") (pintype "passive"))
      (node (ref "J5") (pin "4") (pinfunction "MNT_1_4") (pintype "passive"))
      (node (ref "J5") (pin "5") (pinfunction "MNT_2_5") (pintype "passive"))
      (node (ref "J6") (pin "2") (pinfunction "2_2") (pintype "passive"))
      (node (ref "J7") (pin "2") (pinfunction "2_2") (pintype "passive"))
      (node (ref "Q5") (pin "1") (pinfunction "S1_1") (pintype "passive"))
      (node (ref "Q6") (pin "2") (pinfunction "Source_2") (pintype "passive"))
      (node (ref "R14") (pin "2") (pinfunction "2_2") (pintype "passive"))
      (node (ref "R24") (pin "1") (pinfunction "1_1") (pintype "passive"))
      (node (ref "R26") (pin "1") (pinfunction "1_1") (pintype "passive"))
      (node (ref "R29") (pin "1") (pinfunction "1_1") (pintype "passive"))
      (node (ref "R5") (pin "1") (pinfunction "1_1") (pintype "passive"))
      (node (ref "R6") (pin "2") (pinfunction "2_2") (pintype "passive"))
      (node (ref "R7") (pin "2") (pinfunction "2_2") (pintype "passive"))
      (node (ref "TP10") (pin "1") (pinfunction "1_1") (pintype "passive"))
      (node (ref "TP3") (pin "1") (pinfunction "1_1") (pintype "passive"))
      (node (ref "TP4") (pin "1") (pinfunction "1_1") (pintype "passive"))
      (node (ref "TP7") (pin "1") (pinfunction "1_1") (pintype "passive"))
      (node (ref "U3") (pin "11") (pinfunction "GND_11") (pintype "power_in"))
      (node (ref "U3") (pin "17") (pinfunction "Thermal_Pad_17") (pintype "power_in"))
      (node (ref "U5") (pin "1") (pinfunction "VSS_1") (pintype "power_in"))
      (node (ref "U5") (pin "13") (pinfunction "PWPD_13") (pintype "power_in"))
      (node (ref "U7") (pin "2") (pinfunction "GND_2") (pintype "input"))
      (node (ref "U8") (pin "4") (pinfunction "GND_4") (pintype "power_in"))
    )
    (net (code "29") (name "Net-(C19-Pad1)") (class "Default")
      (node (ref "C19") (pin "1") (pinfunction "1_1") (pintype "passive"))
      (node (ref "C20") (pin "2") (pinfunction "2_2") (pintype "passive"))
    )
    (net (code "30") (name "Net-(C21-Pad2)") (class "Default")
      (node (ref "C21") (pin "2") (pinfunction "2_2") (pintype "passive"))
      (node (ref "C22") (pin "1") (pinfunction "1_1") (pintype "passive"))
    )
    (net (code "31") (name "Net-(C38-Pad1)") (class "Default")
      (node (ref "C38") (pin "1") (pinfunction "1_1") (pintype "passive"))
      (node (ref "R21") (pin "2") (pinfunction "2_2") (pintype "passive"))
    )
    (net (code "32") (name "Net-(D1-K)") (class "Default")
      (node (ref "D1") (pin "1") (pinfunction "K_1") (pintype "passive"))
      (node (ref "R8") (pin "2") (pinfunction "2_2") (pintype "passive"))
      (node (ref "R9") (pin "1") (pinfunction "1_1") (pintype "passive"))
    )
    (net (code "33") (name "Net-(D2-K)") (class "Default")
      (node (ref "D2") (pin "1") (pinfunction "K_1") (pintype "passive"))
      (node (ref "R10") (pin "2") (pinfunction "2_2") (pintype "passive"))
      (node (ref "R11") (pin "1") (pinfunction "1_1") (pintype "passive"))
    )
    (net (code "34") (name "Net-(Q2-Drain)") (class "Default")
      (node (ref "Q2") (pin "3") (pinfunction "Drain_3") (pintype "passive"))
      (node (ref "Q3") (pin "1") (pinfunction "Gate_1") (pintype "passive"))
      (node (ref "R12") (pin "2") (pinfunction "2_2") (pintype "passive"))
      (node (ref "R15") (pin "1") (pinfunction "1_1") (pintype "passive"))
    )
    (net (code "35") (name "Net-(Q2-Gate)") (class "Default")
      (node (ref "Q2") (pin "1") (pinfunction "Gate_1") (pintype "passive"))
      (node (ref "R14") (pin "1") (pinfunction "1_1") (pintype "passive"))
    )
    (net (code "36") (name "Net-(Q3-Drain)") (class "Default")
      (node (ref "Q3") (pin "3") (pinfunction "Drain_3") (pintype "passive"))
      (node (ref "Q4") (pin "3") (pinfunction "Drain_3") (pintype "passive"))
    )
    (net (code "37") (name "Net-(Q4-Gate)") (class "Default")
      (node (ref "Q4") (pin "1") (pinfunction "Gate_1") (pintype "passive"))
      (node (ref "R13") (pin "2") (pinfunction "2_2") (pintype "passive"))
      (node (ref "R16") (pin "1") (pinfunction "1_1") (pintype "passive"))
    )
    (net (code "38") (name "Net-(Q4-Source)") (class "Default")
      (node (ref "C22") (pin "2") (pinfunction "2_2") (pintype "passive"))
      (node (ref "Q4") (pin "2") (pinfunction "Source_2") (pintype "passive"))
      (node (ref "R13") (pin "1") (pinfunction "1_1") (pintype "passive"))
      (node (ref "R32") (pin "1") (pinfunction "1_1") (pintype "passive"))
    )
    (net (code "39") (name "Net-(U3-TERM_EN)") (class "Default")
      (node (ref "C39") (pin "1") (pinfunction "1_1") (pintype "passive"))
      (node (ref "R23") (pin "2") (pinfunction "2_2") (pintype "passive"))
      (node (ref "U3") (pin "6") (pinfunction "VREF_6") (pintype "power_in"))
      (node (ref "U3") (pin "7") (pinfunction "TERM_EN_7") (pintype "input"))
    )
    (net (code "40") (name "Net-(U3-VCC)") (class "Default")
      (node (ref "C37") (pin "1") (pinfunction "1_1") (pintype "passive"))
      (node (ref "R22") (pin "2") (pinfunction "2_2") (pintype "passive"))
      (node (ref "U3") (pin "1") (pinfunction "VCC_1") (pintype "power_in"))
    )
    (net (code "41") (name "Net-(U5-PACK)") (class "Default")
      (node (ref "R17") (pin "1") (pinfunction "1_1") (pintype "passive"))
      (node (ref "U5") (pin "8") (pinfunction "PACK_8") (pintype "input"))
    )
    (net (code "42") (name "Net-(U5-PBI)") (class "Default")
      (node (ref "C18") (pin "2") (pinfunction "2_2") (pintype "passive"))
      (node (ref "U5") (pin "10") (pinfunction "PBI_10") (pintype "power_in"))
    )
    (net (code "43") (name "Net-(U5-SRN)") (class "Default")
      (node (ref "C14") (pin "1") (pinfunction "1_1") (pintype "passive"))
      (node (ref "C17") (pin "2") (pinfunction "2_2") (pintype "passive"))
      (node (ref "R7") (pin "1") (pinfunction "1_1") (pintype "passive"))
      (node (ref "U5") (pin "2") (pinfunction "SRN_2") (pintype "input"))
    )
    (net (code "44") (name "Net-(U5-SRP)") (class "Default")
      (node (ref "C13") (pin "1") (pinfunction "1_1") (pintype "passive"))
      (node (ref "C17") (pin "1") (pinfunction "1_1") (pintype "passive"))
      (node (ref "R6") (pin "1") (pinfunction "1_1") (pintype "passive"))
      (node (ref "U5") (pin "3") (pinfunction "SRP_3") (pintype "input"))
    )
    (net (code "45") (name "Solar+") (class "Default")
      (node (ref "D3") (pin "2") (pinfunction "A_2") (pintype "passive"))
      (node (ref "J6") (pin "1") (pinfunction "1_1") (pintype "passive"))
      (node (ref "R19") (pin "2") (pinfunction "2_2") (pintype "passive"))
      (node (ref "R20") (pin "2") (pinfunction "2_2") (pintype "passive"))
      (node (ref "R21") (pin "1") (pinfunction "1_1") (pintype "passive"))
      (node (ref "TP5") (pin "1") (pinfunction "1_1") (pintype "passive"))
    )
    (net (code "46") (name "unconnected-(U7-N{slash}C-Pad5)") (class "Default")
      (node (ref "U7") (pin "5") (pinfunction "N/C_5") (pintype "input+no_connect"))
    )
  )
)
